# subckt_3V3_SMPS.net
KiCad netlist of a schematic drawn in Altium Designer
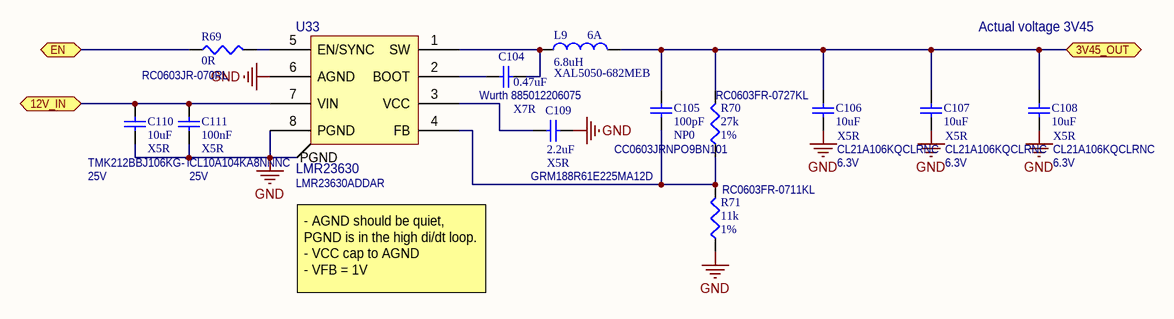
[diagram p0: subckt_3V3_SMPS.SchDoc]

(export (version "E")
  (design (tool "Eeschema 10.0.6"))
  (components
    (comp (ref "C104")
      (value "0.47uF")
      (footprint "CAP0603")
      (description "Capacitor")
      (fields (field (name "DIELECTRIC") "X7R") (field (name "MODEL") "Wurth 885012206075"))
      (libsource (lib "lib_basic") (part "Capacitor"))
    )
    (comp (ref "C105")
      (value "100pF")
      (footprint "CAP0603")
      (description "Capacitor")
      (fields (field (name "DIELECTRIC") "NP0") (field (name "MODEL") "CC0603JRNPO9BN101"))
      (libsource (lib "lib_basic") (part "Capacitor"))
    )
    (comp (ref "C106")
      (value "10uF")
      (footprint "lib_basic:CAP0805")
      (description "Capacitor")
      (fields
        (field (name "DIELECTRIC") "X5R")
        (field (name "MODEL") "CL21A106KQCLRNC")
        (field (name "VOLTAGE") "6.3V")
      )
      (libsource (lib "lib_basic") (part "Capacitor"))
    )
    (comp (ref "C107")
      (value "10uF")
      (footprint "lib_basic:CAP0805")
      (description "Capacitor")
      (fields
        (field (name "DIELECTRIC") "X5R")
        (field (name "MODEL") "CL21A106KQCLRNC")
        (field (name "VOLTAGE") "6.3V")
      )
      (libsource (lib "lib_basic") (part "Capacitor"))
    )
    (comp (ref "C108")
      (value "10uF")
      (footprint "lib_basic:CAP0805")
      (description "Capacitor")
      (fields
        (field (name "DIELECTRIC") "X5R")
        (field (name "MODEL") "CL21A106KQCLRNC")
        (field (name "VOLTAGE") "6.3V")
      )
      (libsource (lib "lib_basic") (part "Capacitor"))
    )
    (comp (ref "C109")
      (value "2.2uF")
      (footprint "CAP0603")
      (description "Capacitor")
      (fields (field (name "DIELECTRIC") "X5R") (field (name "MODEL") "GRM188R61E225MA12D"))
      (libsource (lib "lib_basic") (part "Capacitor"))
    )
    (comp (ref "C110")
      (value "10uF")
      (footprint "lib_basic:CAP0805")
      (description "Capacitor")
      (fields
        (field (name "DIELECTRIC") "X5R")
        (field (name "MODEL") "TMK212BBJ106KG-T")
        (field (name "VOLTAGE") "25V")
      )
      (libsource (lib "lib_basic") (part "Capacitor"))
    )
    (comp (ref "C111")
      (value "100nF")
      (footprint "CAP0603")
      (description "Capacitor")
      (fields
        (field (name "DIELECTRIC") "X5R")
        (field (name "MODEL") "CL10A104KA8NNNC")
        (field (name "VOLTAGE") "25V")
      )
      (libsource (lib "lib_basic") (part "Capacitor"))
    )
    (comp (ref "L9")
      (value "6A")
      (footprint "lib_basic:IND XAL50")
      (description "Inductor")
      (fields (field (name "ALTIUM_VALUE") "6.8uH") (field (name "MODEL") "XAL5050-682MEB"))
      (libsource (lib "lib_basic") (part "Inductor"))
    )
    (comp (ref "R69")
      (value "0R")
      (footprint "RES0603")
      (description "Resistor")
      (fields (field (name "MODEL") "RC0603JR-070RL"))
      (libsource (lib "lib_basic") (part "Resistor"))
    )
    (comp (ref "R70")
      (value "27k")
      (footprint "RES0603")
      (description "Resistor")
      (fields (field (name "TYPE") "1%") (field (name "MODEL") "RC0603FR-0727KL"))
      (libsource (lib "lib_basic") (part "Resistor"))
    )
    (comp (ref "R71")
      (value "11k")
      (footprint "RES0603")
      (description "Resistor")
      (fields (field (name "TYPE") "1%") (field (name "MODEL") "RC0603FR-0711KL"))
      (libsource (lib "lib_basic") (part "Resistor"))
    )
    (comp (ref "U33")
      (value "LMR23630")
      (footprint "lib_basic:SOIC8 Thermal Pad")
      (description "3A Simple Switcher sync buck")
      (fields (field (name "MODEL") "LMR23630ADDAR"))
      (libsource (lib "lib_TI_Power") (part "LMR23630"))
    )
  )
  (nets
    (net (code "1") (name "/3V45_OUT") (class "Default")
      (node (ref "C105") (pin "2") (pinfunction "2_2") (pintype "passive"))
      (node (ref "C106") (pin "2") (pinfunction "2_2") (pintype "passive"))
      (node (ref "C107") (pin "2") (pinfunction "2_2") (pintype "passive"))
      (node (ref "C108") (pin "2") (pinfunction "2_2") (pintype "passive"))
      (node (ref "L9") (pin "2") (pinfunction "2_2") (pintype "passive"))
      (node (ref "R70") (pin "2") (pinfunction "2_2") (pintype "passive"))
    )
    (net (code "2") (name "/12V_IN") (class "Default")
      (node (ref "C110") (pin "2") (pinfunction "2_2") (pintype "passive"))
      (node (ref "C111") (pin "2") (pinfunction "2_2") (pintype "passive"))
      (node (ref "U33") (pin "7") (pinfunction "VIN_7") (pintype "passive"))
    )
    (net (code "3") (name "/EN") (class "Default")
      (node (ref "R69") (pin "1") (pinfunction "1_1") (pintype "passive"))
    )
    (net (code "4") (name "GND") (class "Default")
      (node (ref "C106") (pin "1") (pinfunction "1_1") (pintype "passive"))
      (node (ref "C107") (pin "1") (pinfunction "1_1") (pintype "passive"))
      (node (ref "C108") (pin "1") (pinfunction "1_1") (pintype "passive"))
      (node (ref "C109") (pin "2") (pinfunction "2_2") (pintype "passive"))
      (node (ref "C110") (pin "1") (pinfunction "1_1") (pintype "passive"))
      (node (ref "C111") (pin "1") (pinfunction "1_1") (pintype "passive"))
      (node (ref "R71") (pin "1") (pinfunction "1_1") (pintype "passive"))
      (node (ref "U33") (pin "6") (pinfunction "AGND_6") (pintype "passive"))
      (node (ref "U33") (pin "8") (pinfunction "PGND_8") (pintype "passive"))
      (node (ref "U33") (pin "9") (pinfunction "PGND_9") (pintype "passive"))
    )
    (net (code "5") (name "Net-(U33-BOOT)") (class "Default")
      (node (ref "C104") (pin "2") (pinfunction "2_2") (pintype "passive"))
      (node (ref "U33") (pin "2") (pinfunction "BOOT_2") (pintype "passive"))
    )
    (net (code "6") (name "Net-(U33-EN{slash}SYNC)") (class "Default")
      (node (ref "R69") (pin "2") (pinfunction "2_2") (pintype "passive"))
      (node (ref "U33") (pin "5") (pinfunction "EN/SYNC_5") (pintype "passive"))
    )
    (net (code "7") (name "Net-(U33-FB)") (class "Default")
      (node (ref "C105") (pin "1") (pinfunction "1_1") (pintype "passive"))
      (node (ref "R70") (pin "1") (pinfunction "1_1") (pintype "passive"))
      (node (ref "R71") (pin "2") (pinfunction "2_2") (pintype "passive"))
      (node (ref "U33") (pin "4") (pinfunction "FB_4") (pintype "passive"))
    )
    (net (code "8") (name "Net-(U33-SW)") (class "Default")
      (node (ref "C104") (pin "1") (pinfunction "1_1") (pintype "passive"))
      (node (ref "L9") (pin "1") (pinfunction "1_1") (pintype "passive"))
      (node (ref "U33") (pin "1") (pinfunction "SW_1") (pintype "passive"))
    )
    (net (code "9") (name "Net-(U33-VCC)") (class "Default")
      (node (ref "C109") (pin "1") (pinfunction "1_1") (pintype "passive"))
      (node (ref "U33") (pin "3") (pinfunction "VCC_3") (pintype "passive"))
    )
  )
)
